# SQUAREPOWERVerticalUSBCV1.net
KiCad netlist of a schematic drawn in EAGLE
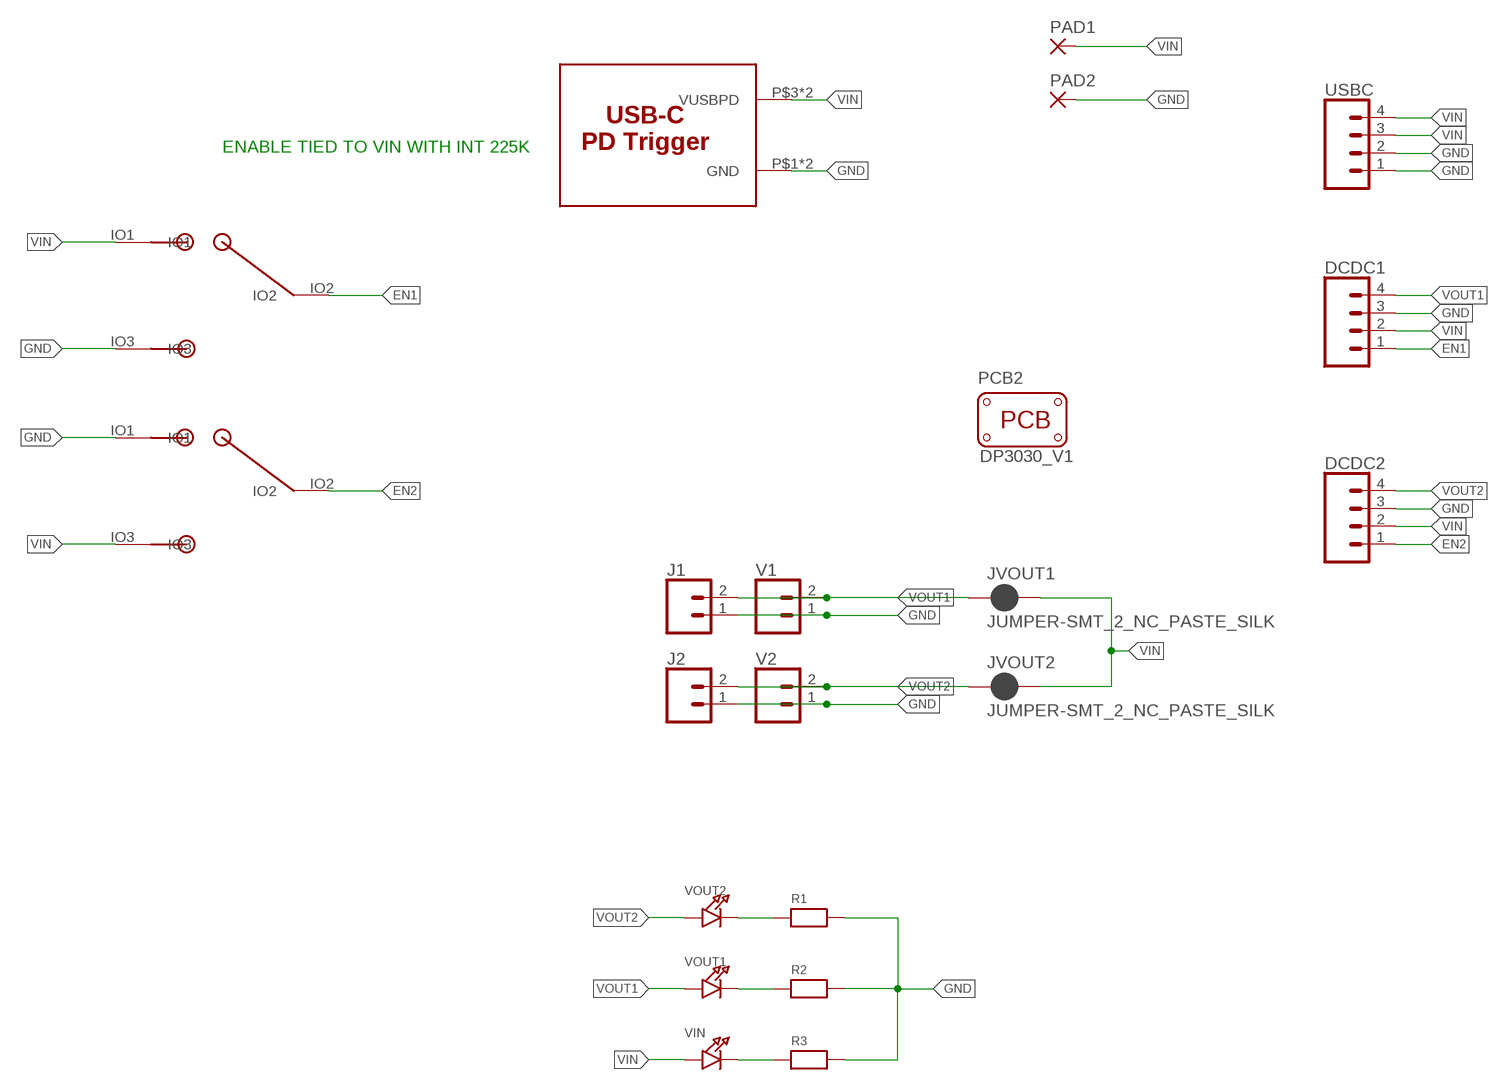
[diagram p0: schematic, sheet 1]

(export (version "E")
  (design (tool "Eeschema 10.0.6"))
  (components
    (comp (ref "DCDC1")
      (value "CONN_04LONGPADS")
      (footprint "eagle-import:1X04_LONGPADS")
      (libsource (lib "eagle-import") (part "CONN_04LONGPADS"))
    )
    (comp (ref "DCDC2")
      (value "CONN_04LONGPADS")
      (footprint "eagle-import:1X04_LONGPADS")
      (libsource (lib "eagle-import") (part "CONN_04LONGPADS"))
    )
    (comp (ref "J1")
      (value "CONN_02")
      (footprint "eagle-import:1X02")
      (libsource (lib "eagle-import") (part "CONN_02"))
    )
    (comp (ref "J2")
      (value "CONN_02")
      (footprint "eagle-import:1X02")
      (libsource (lib "eagle-import") (part "CONN_02"))
    )
    (comp (ref "JVOUT1")
      (value "JUMPER-SMT_2_NC_PASTE_SILK")
      (footprint "eagle-import:SMT-JUMPER_2_NC_PASTE_SILK")
      (libsource (lib "eagle-import") (part "JUMPER-SMT_2_NC_PASTE_SILK"))
    )
    (comp (ref "JVOUT2")
      (value "JUMPER-SMT_2_NC_PASTE_SILK")
      (footprint "eagle-import:SMT-JUMPER_2_NC_PASTE_SILK")
      (libsource (lib "eagle-import") (part "JUMPER-SMT_2_NC_PASTE_SILK"))
    )
    (comp (ref "PAD1")
      (value "SMD5")
      (footprint "eagle-import:SMD2,54-5,08")
      (libsource (lib "eagle-import") (part "SMD5"))
    )
    (comp (ref "PAD2")
      (value "SMD5")
      (footprint "eagle-import:SMD2,54-5,08")
      (libsource (lib "eagle-import") (part "SMD5"))
    )
    (comp (ref "PCB2")
      (value "PCB_DP_SQUARE-3X3")
      (footprint "eagle-import:DP3030_V1")
      (fields (field (name "PCB_SIZE") "DP3030_V1"))
      (libsource (lib "eagle-import") (part "PCB_DP_SQUARE-3X3"))
    )
    (comp (ref "R1")
      (value "RESISTOR0805")
      (footprint "eagle-import:0805")
      (libsource (lib "eagle-import") (part "RESISTOR0805"))
    )
    (comp (ref "R2")
      (value "RESISTOR0805")
      (footprint "eagle-import:0805")
      (libsource (lib "eagle-import") (part "RESISTOR0805"))
    )
    (comp (ref "R3")
      (value "RESISTOR0805")
      (footprint "eagle-import:0805")
      (libsource (lib "eagle-import") (part "RESISTOR0805"))
    )
    (comp (ref "U$1")
      (value "SPDT-SWITCH-MSKT-12C00")
      (footprint "eagle-import:MSKT-12C00")
      (libsource (lib "eagle-import") (part "SPDT-SWITCH-MSKT-12C00"))
    )
    (comp (ref "U$2")
      (value "SPDT-SWITCH-MSKT-12C00")
      (footprint "eagle-import:MSKT-12C00")
      (libsource (lib "eagle-import") (part "SPDT-SWITCH-MSKT-12C00"))
    )
    (comp (ref "U$5")
      (value "USB_PD_TRIGGER")
      (footprint "eagle-import:USB-PDTRIGGER")
      (libsource (lib "eagle-import") (part "USB_PD_TRIGGER"))
    )
    (comp (ref "USBC")
      (value "CONN_04LONGPADS")
      (footprint "eagle-import:1X04_LONGPADS")
      (libsource (lib "eagle-import") (part "CONN_04LONGPADS"))
    )
    (comp (ref "V1")
      (value "CONN_023.5MM")
      (footprint "eagle-import:SCREWTERMINAL-3.5MM-2")
      (libsource (lib "eagle-import") (part "CONN_023.5MM"))
    )
    (comp (ref "V2")
      (value "CONN_023.5MM")
      (footprint "eagle-import:SCREWTERMINAL-3.5MM-2")
      (libsource (lib "eagle-import") (part "CONN_023.5MM"))
    )
    (comp (ref "VIN")
      (value "LED0805")
      (footprint "eagle-import:CHIPLED_0805")
      (libsource (lib "eagle-import") (part "LED0805"))
    )
    (comp (ref "VOUT1")
      (value "LED0805")
      (footprint "eagle-import:CHIPLED_0805")
      (libsource (lib "eagle-import") (part "LED0805"))
    )
    (comp (ref "VOUT2")
      (value "LED0805")
      (footprint "eagle-import:CHIPLED_0805")
      (libsource (lib "eagle-import") (part "LED0805"))
    )
  )
  (nets
    (net (code "1") (name "EN1") (class "Default")
      (node (ref "DCDC1") (pin "1") (pinfunction "1_1") (pintype "passive"))
      (node (ref "U$1") (pin "IO2") (pinfunction "IO2_IO2") (pintype "bidirectional"))
    )
    (net (code "2") (name "EN2") (class "Default")
      (node (ref "DCDC2") (pin "1") (pinfunction "1_1") (pintype "passive"))
      (node (ref "U$2") (pin "IO2") (pinfunction "IO2_IO2") (pintype "bidirectional"))
    )
    (net (code "3") (name "GND") (class "Default")
      (node (ref "DCDC1") (pin "3") (pinfunction "3_3") (pintype "passive"))
      (node (ref "DCDC2") (pin "3") (pinfunction "3_3") (pintype "passive"))
      (node (ref "J1") (pin "1") (pinfunction "1_1") (pintype "passive"))
      (node (ref "J2") (pin "1") (pinfunction "1_1") (pintype "passive"))
      (node (ref "PAD2") (pin "1") (pinfunction "P_1") (pintype "passive"))
      (node (ref "R1") (pin "2") (pinfunction "2_2") (pintype "passive"))
      (node (ref "R2") (pin "2") (pinfunction "2_2") (pintype "passive"))
      (node (ref "R3") (pin "2") (pinfunction "2_2") (pintype "passive"))
      (node (ref "U$1") (pin "IO3") (pinfunction "IO3_IO3") (pintype "bidirectional"))
      (node (ref "U$2") (pin "IO1") (pinfunction "IO1_IO1") (pintype "bidirectional"))
      (node (ref "U$5") (pin "P$1") (pinfunction "GND_P$1") (pintype "bidirectional"))
      (node (ref "U$5") (pin "P$2") (pinfunction "GND_P$2") (pintype "bidirectional"))
      (node (ref "USBC") (pin "1") (pinfunction "1_1") (pintype "passive"))
      (node (ref "USBC") (pin "2") (pinfunction "2_2") (pintype "passive"))
      (node (ref "V1") (pin "1") (pinfunction "1_1") (pintype "passive"))
      (node (ref "V2") (pin "1") (pinfunction "1_1") (pintype "passive"))
    )
    (net (code "4") (name "Net-(R1-Pad1)") (class "Default")
      (node (ref "R1") (pin "1") (pinfunction "1_1") (pintype "passive"))
      (node (ref "VOUT2") (pin "C") (pinfunction "C_C") (pintype "passive"))
    )
    (net (code "5") (name "Net-(R2-Pad1)") (class "Default")
      (node (ref "R2") (pin "1") (pinfunction "1_1") (pintype "passive"))
      (node (ref "VOUT1") (pin "C") (pinfunction "C_C") (pintype "passive"))
    )
    (net (code "6") (name "Net-(R3-Pad1)") (class "Default")
      (node (ref "R3") (pin "1") (pinfunction "1_1") (pintype "passive"))
      (node (ref "VIN") (pin "C") (pinfunction "C_C") (pintype "passive"))
    )
    (net (code "7") (name "VIN") (class "Default")
      (node (ref "DCDC1") (pin "2") (pinfunction "2_2") (pintype "passive"))
      (node (ref "DCDC2") (pin "2") (pinfunction "2_2") (pintype "passive"))
      (node (ref "JVOUT1") (pin "2") (pinfunction "2_2") (pintype "passive"))
      (node (ref "JVOUT2") (pin "2") (pinfunction "2_2") (pintype "passive"))
      (node (ref "PAD1") (pin "1") (pinfunction "P_1") (pintype "passive"))
      (node (ref "U$1") (pin "IO1") (pinfunction "IO1_IO1") (pintype "bidirectional"))
      (node (ref "U$2") (pin "IO3") (pinfunction "IO3_IO3") (pintype "bidirectional"))
      (node (ref "U$5") (pin "P$3") (pinfunction "VUSBPD_P$3") (pintype "bidirectional"))
      (node (ref "U$5") (pin "P$4") (pinfunction "VUSBPD_P$4") (pintype "bidirectional"))
      (node (ref "USBC") (pin "3") (pinfunction "3_3") (pintype "passive"))
      (node (ref "USBC") (pin "4") (pinfunction "4_4") (pintype "passive"))
      (node (ref "VIN") (pin "A") (pinfunction "A_A") (pintype "passive"))
    )
    (net (code "8") (name "VOUT1") (class "Default")
      (node (ref "DCDC1") (pin "4") (pinfunction "4_4") (pintype "passive"))
      (node (ref "J1") (pin "2") (pinfunction "2_2") (pintype "passive"))
      (node (ref "JVOUT1") (pin "1") (pinfunction "1_1") (pintype "passive"))
      (node (ref "V1") (pin "2") (pinfunction "2_2") (pintype "passive"))
      (node (ref "VOUT1") (pin "A") (pinfunction "A_A") (pintype "passive"))
    )
    (net (code "9") (name "VOUT2") (class "Default")
      (node (ref "DCDC2") (pin "4") (pinfunction "4_4") (pintype "passive"))
      (node (ref "J2") (pin "2") (pinfunction "2_2") (pintype "passive"))
      (node (ref "JVOUT2") (pin "1") (pinfunction "1_1") (pintype "passive"))
      (node (ref "V2") (pin "2") (pinfunction "2_2") (pintype "passive"))
      (node (ref "VOUT2") (pin "A") (pinfunction "A_A") (pintype "passive"))
    )
  )
)
